# power_supply.net
KiCad netlist of a schematic drawn in EAGLE
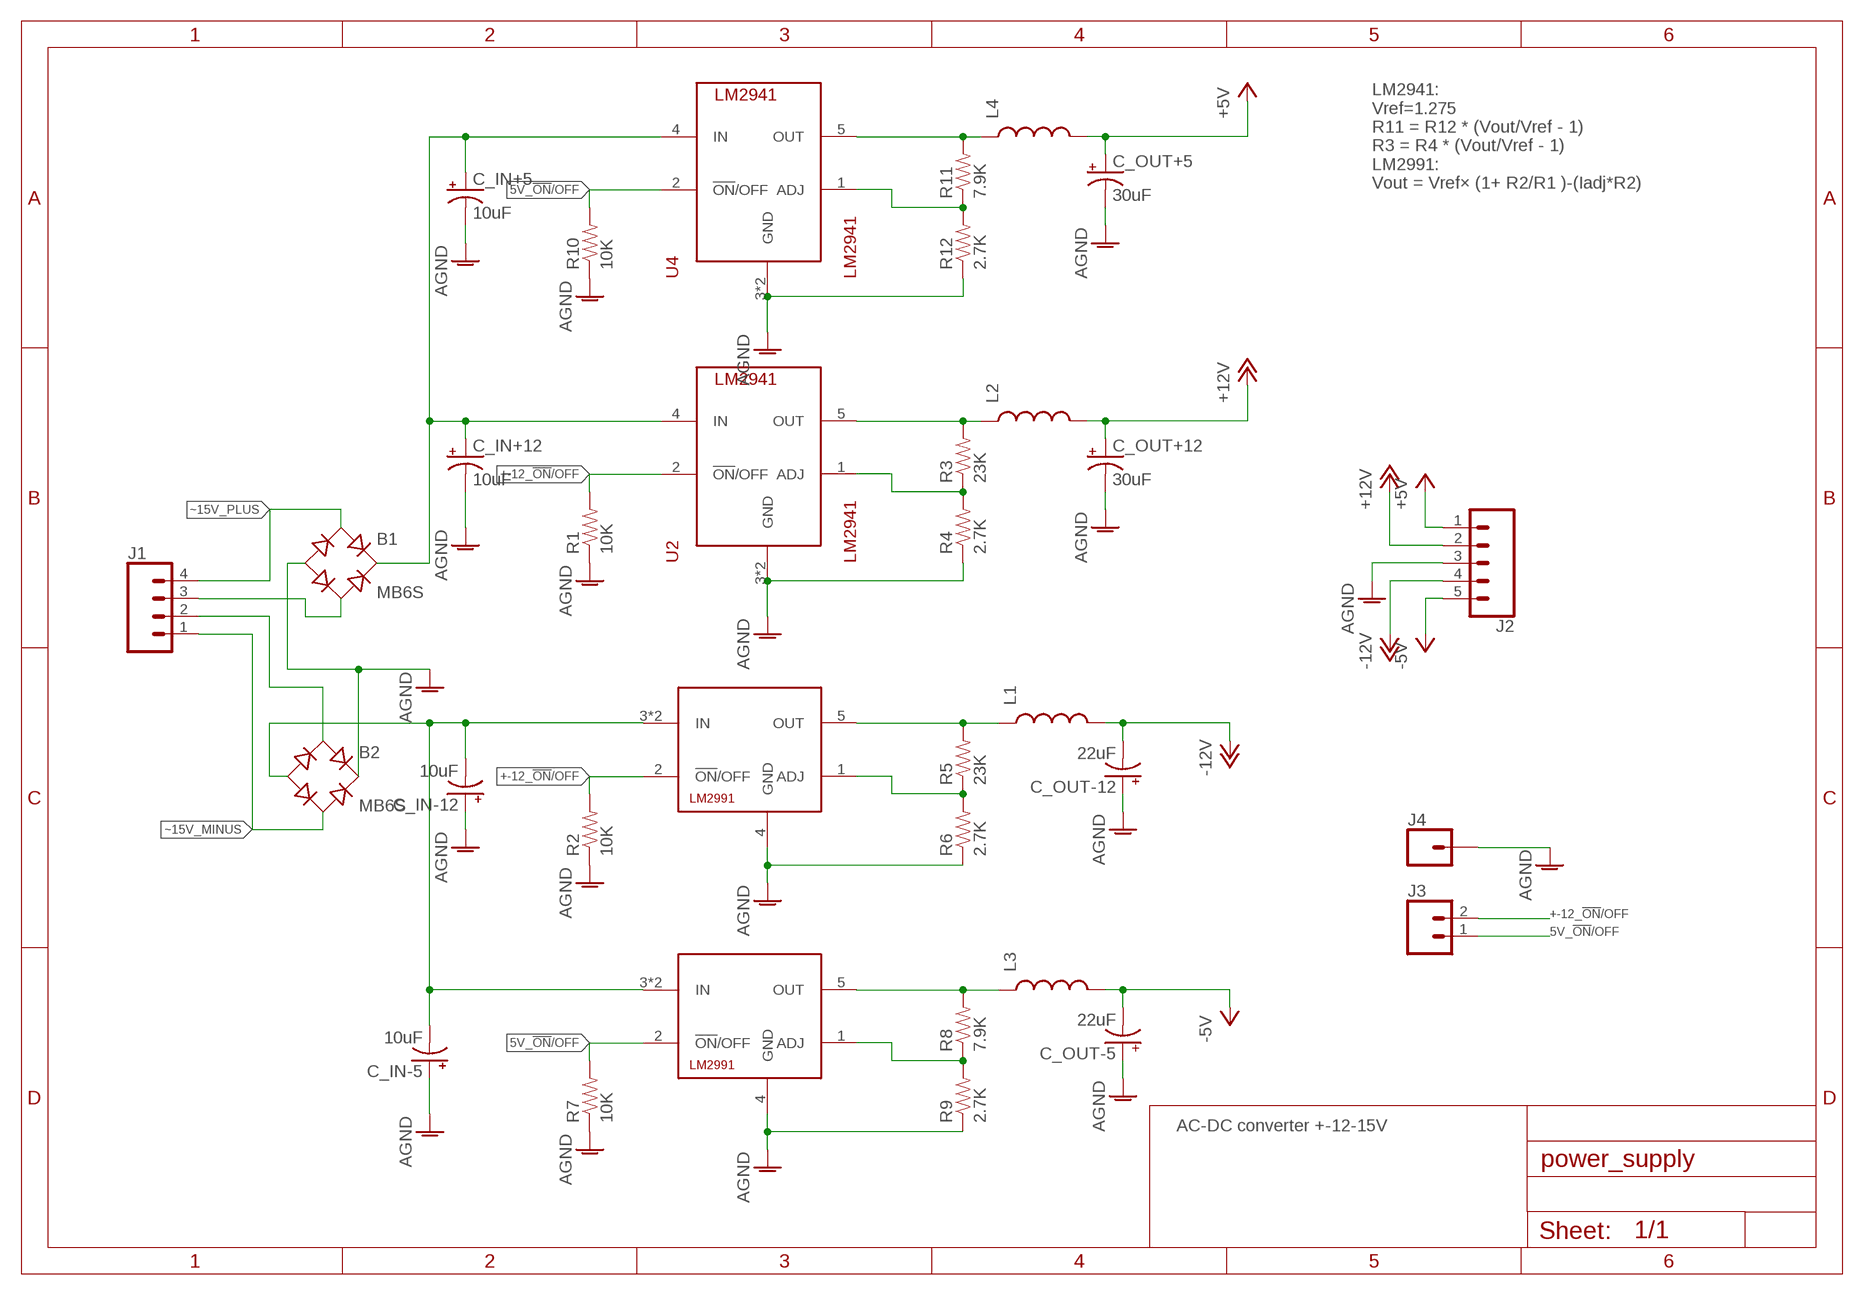
[diagram p0: schematic, sheet 1]

(export (version "E")
  (design (tool "Eeschema 10.0.6"))
  (components
    (comp (ref "B1")
      (value "MB6S")
      (footprint "eagle-import:SOIC-4")
      (libsource (lib "eagle-import") (part "MBS6"))
    )
    (comp (ref "B2")
      (value "MB6S")
      (footprint "eagle-import:SOIC-4")
      (libsource (lib "eagle-import") (part "MBS6"))
    )
    (comp (ref "C_IN+5")
      (value "10uF")
      (footprint "eagle-import:EIA3216")
      (libsource (lib "eagle-import") (part "CAP_POL1206"))
    )
    (comp (ref "C_IN+12")
      (value "10uF")
      (footprint "eagle-import:EIA3216")
      (libsource (lib "eagle-import") (part "CAP_POL1206"))
    )
    (comp (ref "C_IN-5")
      (value "10uF")
      (footprint "eagle-import:EIA3216")
      (libsource (lib "eagle-import") (part "CAP_POL1206"))
    )
    (comp (ref "C_IN-12")
      (value "10uF")
      (footprint "eagle-import:EIA3216")
      (libsource (lib "eagle-import") (part "CAP_POL1206"))
    )
    (comp (ref "C_OUT+5")
      (value "30uF")
      (footprint "eagle-import:CPOL-RADIAL-100UF-25V")
      (libsource (lib "eagle-import") (part "CAP_POLPTH1"))
    )
    (comp (ref "C_OUT+12")
      (value "30uF")
      (footprint "eagle-import:CPOL-RADIAL-100UF-25V")
      (libsource (lib "eagle-import") (part "CAP_POLPTH1"))
    )
    (comp (ref "C_OUT-5")
      (value "22uF")
      (footprint "eagle-import:CPOL-RADIAL-100UF-25V")
      (libsource (lib "eagle-import") (part "CAP_POLPTH1"))
    )
    (comp (ref "C_OUT-12")
      (value "22uF")
      (footprint "eagle-import:CPOL-RADIAL-100UF-25V")
      (libsource (lib "eagle-import") (part "CAP_POLPTH1"))
    )
    (comp (ref "J1")
      (value "CONN_04LONGPADS")
      (footprint "eagle-import:1X04_LONGPADS")
      (libsource (lib "eagle-import") (part "CONN_04LONGPADS"))
    )
    (comp (ref "J2")
      (value "CONN_05PTH_LONGPADS")
      (footprint "eagle-import:1X05_LONGPADS")
      (libsource (lib "eagle-import") (part "CONN_05PTH_LONGPADS"))
    )
    (comp (ref "J3")
      (value "CONN_02POLAR")
      (footprint "eagle-import:MOLEX-1X2")
      (libsource (lib "eagle-import") (part "CONN_02POLAR"))
    )
    (comp (ref "J4")
      (value "CONN_01")
      (footprint "eagle-import:1X01")
      (libsource (lib "eagle-import") (part "CONN_01"))
    )
    (comp (ref "L1")
      (value "INDUCTOR1206H*")
      (footprint "eagle-import:INDUCTOR-1206")
      (libsource (lib "eagle-import") (part "INDUCTORH1206"))
    )
    (comp (ref "L2")
      (value "INDUCTOR1206H*")
      (footprint "eagle-import:INDUCTOR-1206")
      (libsource (lib "eagle-import") (part "INDUCTORH1206"))
    )
    (comp (ref "L3")
      (value "INDUCTOR1206H*")
      (footprint "eagle-import:INDUCTOR-1206")
      (libsource (lib "eagle-import") (part "INDUCTORH1206"))
    )
    (comp (ref "L4")
      (value "INDUCTOR1206H*")
      (footprint "eagle-import:INDUCTOR-1206")
      (libsource (lib "eagle-import") (part "INDUCTORH1206"))
    )
    (comp (ref "R1")
      (value "10K")
      (footprint "eagle-import:0805")
      (libsource (lib "eagle-import") (part "RESISTOR0805-RES"))
    )
    (comp (ref "R2")
      (value "10K")
      (footprint "eagle-import:0805")
      (libsource (lib "eagle-import") (part "RESISTOR0805-RES"))
    )
    (comp (ref "R3")
      (value "23K")
      (footprint "eagle-import:0805")
      (libsource (lib "eagle-import") (part "RESISTOR0805-RES"))
    )
    (comp (ref "R4")
      (value "2.7K")
      (footprint "eagle-import:0805")
      (libsource (lib "eagle-import") (part "RESISTOR0805-RES"))
    )
    (comp (ref "R5")
      (value "23K")
      (footprint "eagle-import:0805")
      (libsource (lib "eagle-import") (part "RESISTOR0805-RES"))
    )
    (comp (ref "R6")
      (value "2.7K")
      (footprint "eagle-import:0805")
      (libsource (lib "eagle-import") (part "RESISTOR0805-RES"))
    )
    (comp (ref "R7")
      (value "10K")
      (footprint "eagle-import:0805")
      (libsource (lib "eagle-import") (part "RESISTOR0805-RES"))
    )
    (comp (ref "R8")
      (value "7.9K")
      (footprint "eagle-import:0805")
      (libsource (lib "eagle-import") (part "RESISTOR0805-RES"))
    )
    (comp (ref "R9")
      (value "2.7K")
      (footprint "eagle-import:0805")
      (libsource (lib "eagle-import") (part "RESISTOR0805-RES"))
    )
    (comp (ref "R10")
      (value "10K")
      (footprint "eagle-import:0805")
      (libsource (lib "eagle-import") (part "RESISTOR0805-RES"))
    )
    (comp (ref "R11")
      (value "7.9K")
      (footprint "eagle-import:0805")
      (libsource (lib "eagle-import") (part "RESISTOR0805-RES"))
    )
    (comp (ref "R12")
      (value "2.7K")
      (footprint "eagle-import:0805")
      (libsource (lib "eagle-import") (part "RESISTOR0805-RES"))
    )
    (comp (ref "U1")
      (value "LM2991")
      (footprint "eagle-import:DDPAK_TO-263")
      (libsource (lib "eagle-import") (part "LM2991"))
    )
    (comp (ref "U2")
      (value "LM2941")
      (footprint "eagle-import:DDPAK_TO-263")
      (libsource (lib "eagle-import") (part "LM2941"))
    )
    (comp (ref "U3")
      (value "LM2991")
      (footprint "eagle-import:DDPAK_TO-263")
      (libsource (lib "eagle-import") (part "LM2991"))
    )
    (comp (ref "U4")
      (value "LM2941")
      (footprint "eagle-import:DDPAK_TO-263")
      (libsource (lib "eagle-import") (part "LM2941"))
    )
  )
  (nets
    (net (code "1") (name "+5V") (class "Default")
      (node (ref "C_OUT+5") (pin "1") (pinfunction "+_1") (pintype "passive"))
      (node (ref "J2") (pin "1") (pinfunction "1_1") (pintype "passive"))
      (node (ref "L4") (pin "P$2") (pinfunction "2_P$2") (pintype "passive"))
    )
    (net (code "2") (name "+12V") (class "Default")
      (node (ref "C_OUT+12") (pin "1") (pinfunction "+_1") (pintype "passive"))
      (node (ref "J2") (pin "2") (pinfunction "2_2") (pintype "passive"))
      (node (ref "L2") (pin "P$2") (pinfunction "2_P$2") (pintype "passive"))
    )
    (net (code "3") (name "-5V") (class "Default")
      (node (ref "C_OUT-5") (pin "2") (pinfunction "-_2") (pintype "passive"))
      (node (ref "J2") (pin "5") (pinfunction "5_5") (pintype "passive"))
      (node (ref "L3") (pin "P$2") (pinfunction "2_P$2") (pintype "passive"))
    )
    (net (code "4") (name "-12V") (class "Default")
      (node (ref "C_OUT-12") (pin "2") (pinfunction "-_2") (pintype "passive"))
      (node (ref "J2") (pin "4") (pinfunction "4_4") (pintype "passive"))
      (node (ref "L1") (pin "P$2") (pinfunction "2_P$2") (pintype "passive"))
    )
    (net (code "5") (name "/+-12_~{ON}{slash}OFF") (class "Default")
      (node (ref "J3") (pin "2") (pinfunction "2_2") (pintype "passive"))
      (node (ref "R1") (pin "2") (pinfunction "2_2") (pintype "passive"))
      (node (ref "R2") (pin "2") (pinfunction "2_2") (pintype "passive"))
      (node (ref "U1") (pin "2") (pinfunction "~{ON}/OFF_2") (pintype "input"))
      (node (ref "U2") (pin "2") (pinfunction "~{ON}/OFF_2") (pintype "bidirectional"))
    )
    (net (code "6") (name "/5V_~{ON}{slash}OFF") (class "Default")
      (node (ref "J3") (pin "1") (pinfunction "1_1") (pintype "passive"))
      (node (ref "R10") (pin "2") (pinfunction "2_2") (pintype "passive"))
      (node (ref "R7") (pin "2") (pinfunction "2_2") (pintype "passive"))
      (node (ref "U3") (pin "2") (pinfunction "~{ON}/OFF_2") (pintype "input"))
      (node (ref "U4") (pin "2") (pinfunction "~{ON}/OFF_2") (pintype "bidirectional"))
    )
    (net (code "7") (name "/~{15V_MINUS}") (class "Default")
      (node (ref "B2") (pin "~2") (pinfunction "AC2_~2") (pintype "passive"))
      (node (ref "J1") (pin "1") (pinfunction "1_1") (pintype "passive"))
    )
    (net (code "8") (name "/~{15V_PLUS}") (class "Default")
      (node (ref "B1") (pin "~1") (pinfunction "AC1_~1") (pintype "passive"))
      (node (ref "J1") (pin "4") (pinfunction "4_4") (pintype "passive"))
    )
    (net (code "9") (name "AGND") (class "Default")
      (node (ref "B1") (pin "-") (pinfunction "-_-") (pintype "passive"))
      (node (ref "B2") (pin "+") (pinfunction "+_+") (pintype "passive"))
      (node (ref "C_IN+12") (pin "C") (pinfunction "-_C") (pintype "passive"))
      (node (ref "C_IN+5") (pin "C") (pinfunction "-_C") (pintype "passive"))
      (node (ref "C_IN-12") (pin "A") (pinfunction "+_A") (pintype "passive"))
      (node (ref "C_IN-5") (pin "A") (pinfunction "+_A") (pintype "passive"))
      (node (ref "C_OUT+12") (pin "2") (pinfunction "-_2") (pintype "passive"))
      (node (ref "C_OUT+5") (pin "2") (pinfunction "-_2") (pintype "passive"))
      (node (ref "C_OUT-12") (pin "1") (pinfunction "+_1") (pintype "passive"))
      (node (ref "C_OUT-5") (pin "1") (pinfunction "+_1") (pintype "passive"))
      (node (ref "J2") (pin "3") (pinfunction "3_3") (pintype "passive"))
      (node (ref "J4") (pin "1") (pinfunction "1_1") (pintype "passive"))
      (node (ref "R1") (pin "1") (pinfunction "1_1") (pintype "passive"))
      (node (ref "R10") (pin "1") (pinfunction "1_1") (pintype "passive"))
      (node (ref "R12") (pin "1") (pinfunction "1_1") (pintype "passive"))
      (node (ref "R2") (pin "1") (pinfunction "1_1") (pintype "passive"))
      (node (ref "R4") (pin "1") (pinfunction "1_1") (pintype "passive"))
      (node (ref "R6") (pin "1") (pinfunction "1_1") (pintype "passive"))
      (node (ref "R7") (pin "1") (pinfunction "1_1") (pintype "passive"))
      (node (ref "R9") (pin "1") (pinfunction "1_1") (pintype "passive"))
      (node (ref "U1") (pin "4") (pinfunction "GND_4") (pintype "power_in"))
      (node (ref "U2") (pin "3") (pinfunction "GND_3") (pintype "bidirectional"))
      (node (ref "U2") (pin "TAB") (pinfunction "GND_TAB") (pintype "bidirectional"))
      (node (ref "U3") (pin "4") (pinfunction "GND_4") (pintype "power_in"))
      (node (ref "U4") (pin "3") (pinfunction "GND_3") (pintype "bidirectional"))
      (node (ref "U4") (pin "TAB") (pinfunction "GND_TAB") (pintype "bidirectional"))
    )
    (net (code "10") (name "Net-(B1-AC2)") (class "Default")
      (node (ref "B1") (pin "~2") (pinfunction "AC2_~2") (pintype "passive"))
      (node (ref "J1") (pin "3") (pinfunction "3_3") (pintype "passive"))
    )
    (net (code "11") (name "Net-(B2-AC1)") (class "Default")
      (node (ref "B2") (pin "~1") (pinfunction "AC1_~1") (pintype "passive"))
      (node (ref "J1") (pin "2") (pinfunction "2_2") (pintype "passive"))
    )
    (net (code "12") (name "Net-(C_IN+12-+)") (class "Default")
      (node (ref "B1") (pin "+") (pinfunction "+_+") (pintype "passive"))
      (node (ref "C_IN+12") (pin "A") (pinfunction "+_A") (pintype "passive"))
      (node (ref "C_IN+5") (pin "A") (pinfunction "+_A") (pintype "passive"))
      (node (ref "U2") (pin "4") (pinfunction "IN_4") (pintype "bidirectional"))
      (node (ref "U4") (pin "4") (pinfunction "IN_4") (pintype "bidirectional"))
    )
    (net (code "13") (name "Net-(C_IN-12--)") (class "Default")
      (node (ref "B2") (pin "-") (pinfunction "-_-") (pintype "passive"))
      (node (ref "C_IN-12") (pin "C") (pinfunction "-_C") (pintype "passive"))
      (node (ref "C_IN-5") (pin "C") (pinfunction "-_C") (pintype "passive"))
      (node (ref "U1") (pin "3") (pinfunction "IN_3") (pintype "input"))
      (node (ref "U1") (pin "TAB") (pinfunction "IN_TAB") (pintype "input"))
      (node (ref "U3") (pin "3") (pinfunction "IN_3") (pintype "input"))
      (node (ref "U3") (pin "TAB") (pinfunction "IN_TAB") (pintype "input"))
    )
    (net (code "14") (name "Net-(L1-1)") (class "Default")
      (node (ref "L1") (pin "P$1") (pinfunction "1_P$1") (pintype "passive"))
      (node (ref "R5") (pin "2") (pinfunction "2_2") (pintype "passive"))
      (node (ref "U1") (pin "5") (pinfunction "OUT_5") (pintype "output"))
    )
    (net (code "15") (name "Net-(L2-1)") (class "Default")
      (node (ref "L2") (pin "P$1") (pinfunction "1_P$1") (pintype "passive"))
      (node (ref "R3") (pin "2") (pinfunction "2_2") (pintype "passive"))
      (node (ref "U2") (pin "5") (pinfunction "OUT_5") (pintype "bidirectional"))
    )
    (net (code "16") (name "Net-(L3-1)") (class "Default")
      (node (ref "L3") (pin "P$1") (pinfunction "1_P$1") (pintype "passive"))
      (node (ref "R8") (pin "2") (pinfunction "2_2") (pintype "passive"))
      (node (ref "U3") (pin "5") (pinfunction "OUT_5") (pintype "output"))
    )
    (net (code "17") (name "Net-(L4-1)") (class "Default")
      (node (ref "L4") (pin "P$1") (pinfunction "1_P$1") (pintype "passive"))
      (node (ref "R11") (pin "2") (pinfunction "2_2") (pintype "passive"))
      (node (ref "U4") (pin "5") (pinfunction "OUT_5") (pintype "bidirectional"))
    )
    (net (code "18") (name "Net-(U1-ADJ)") (class "Default")
      (node (ref "R5") (pin "1") (pinfunction "1_1") (pintype "passive"))
      (node (ref "R6") (pin "2") (pinfunction "2_2") (pintype "passive"))
      (node (ref "U1") (pin "1") (pinfunction "ADJ_1") (pintype "input"))
    )
    (net (code "19") (name "Net-(U2-ADJ)") (class "Default")
      (node (ref "R3") (pin "1") (pinfunction "1_1") (pintype "passive"))
      (node (ref "R4") (pin "2") (pinfunction "2_2") (pintype "passive"))
      (node (ref "U2") (pin "1") (pinfunction "ADJ_1") (pintype "bidirectional"))
    )
    (net (code "20") (name "Net-(U3-ADJ)") (class "Default")
      (node (ref "R8") (pin "1") (pinfunction "1_1") (pintype "passive"))
      (node (ref "R9") (pin "2") (pinfunction "2_2") (pintype "passive"))
      (node (ref "U3") (pin "1") (pinfunction "ADJ_1") (pintype "input"))
    )
    (net (code "21") (name "Net-(U4-ADJ)") (class "Default")
      (node (ref "R11") (pin "1") (pinfunction "1_1") (pintype "passive"))
      (node (ref "R12") (pin "2") (pinfunction "2_2") (pintype "passive"))
      (node (ref "U4") (pin "1") (pinfunction "ADJ_1") (pintype "bidirectional"))
    )
  )
)
